# ETAG_v10_3_NOSDTRANS.net
KiCad netlist of a schematic drawn in EAGLE
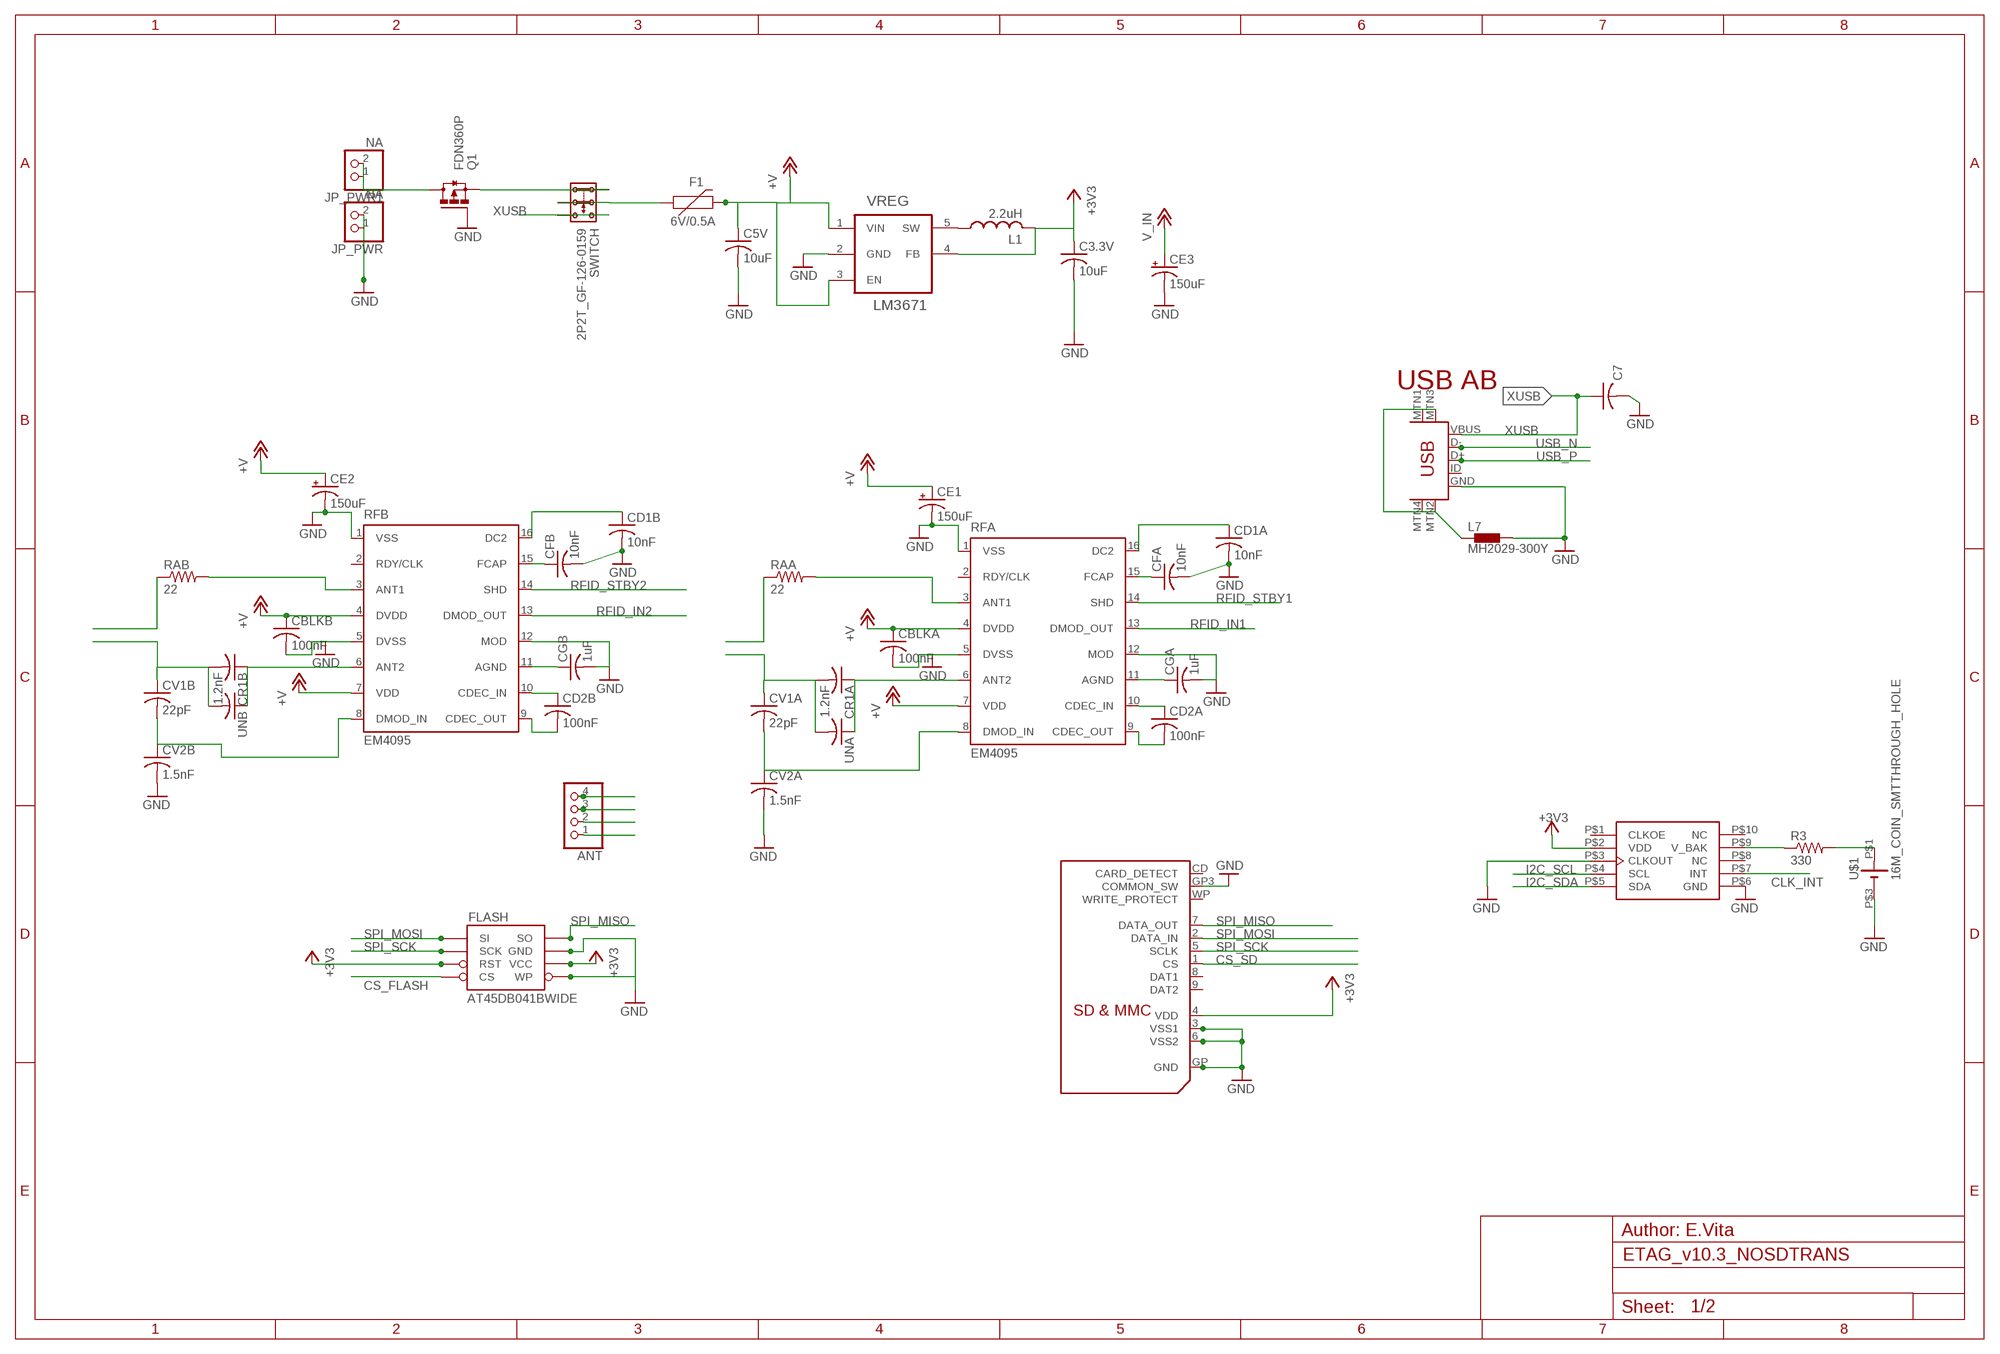
[diagram p0: schematic, sheet 1]
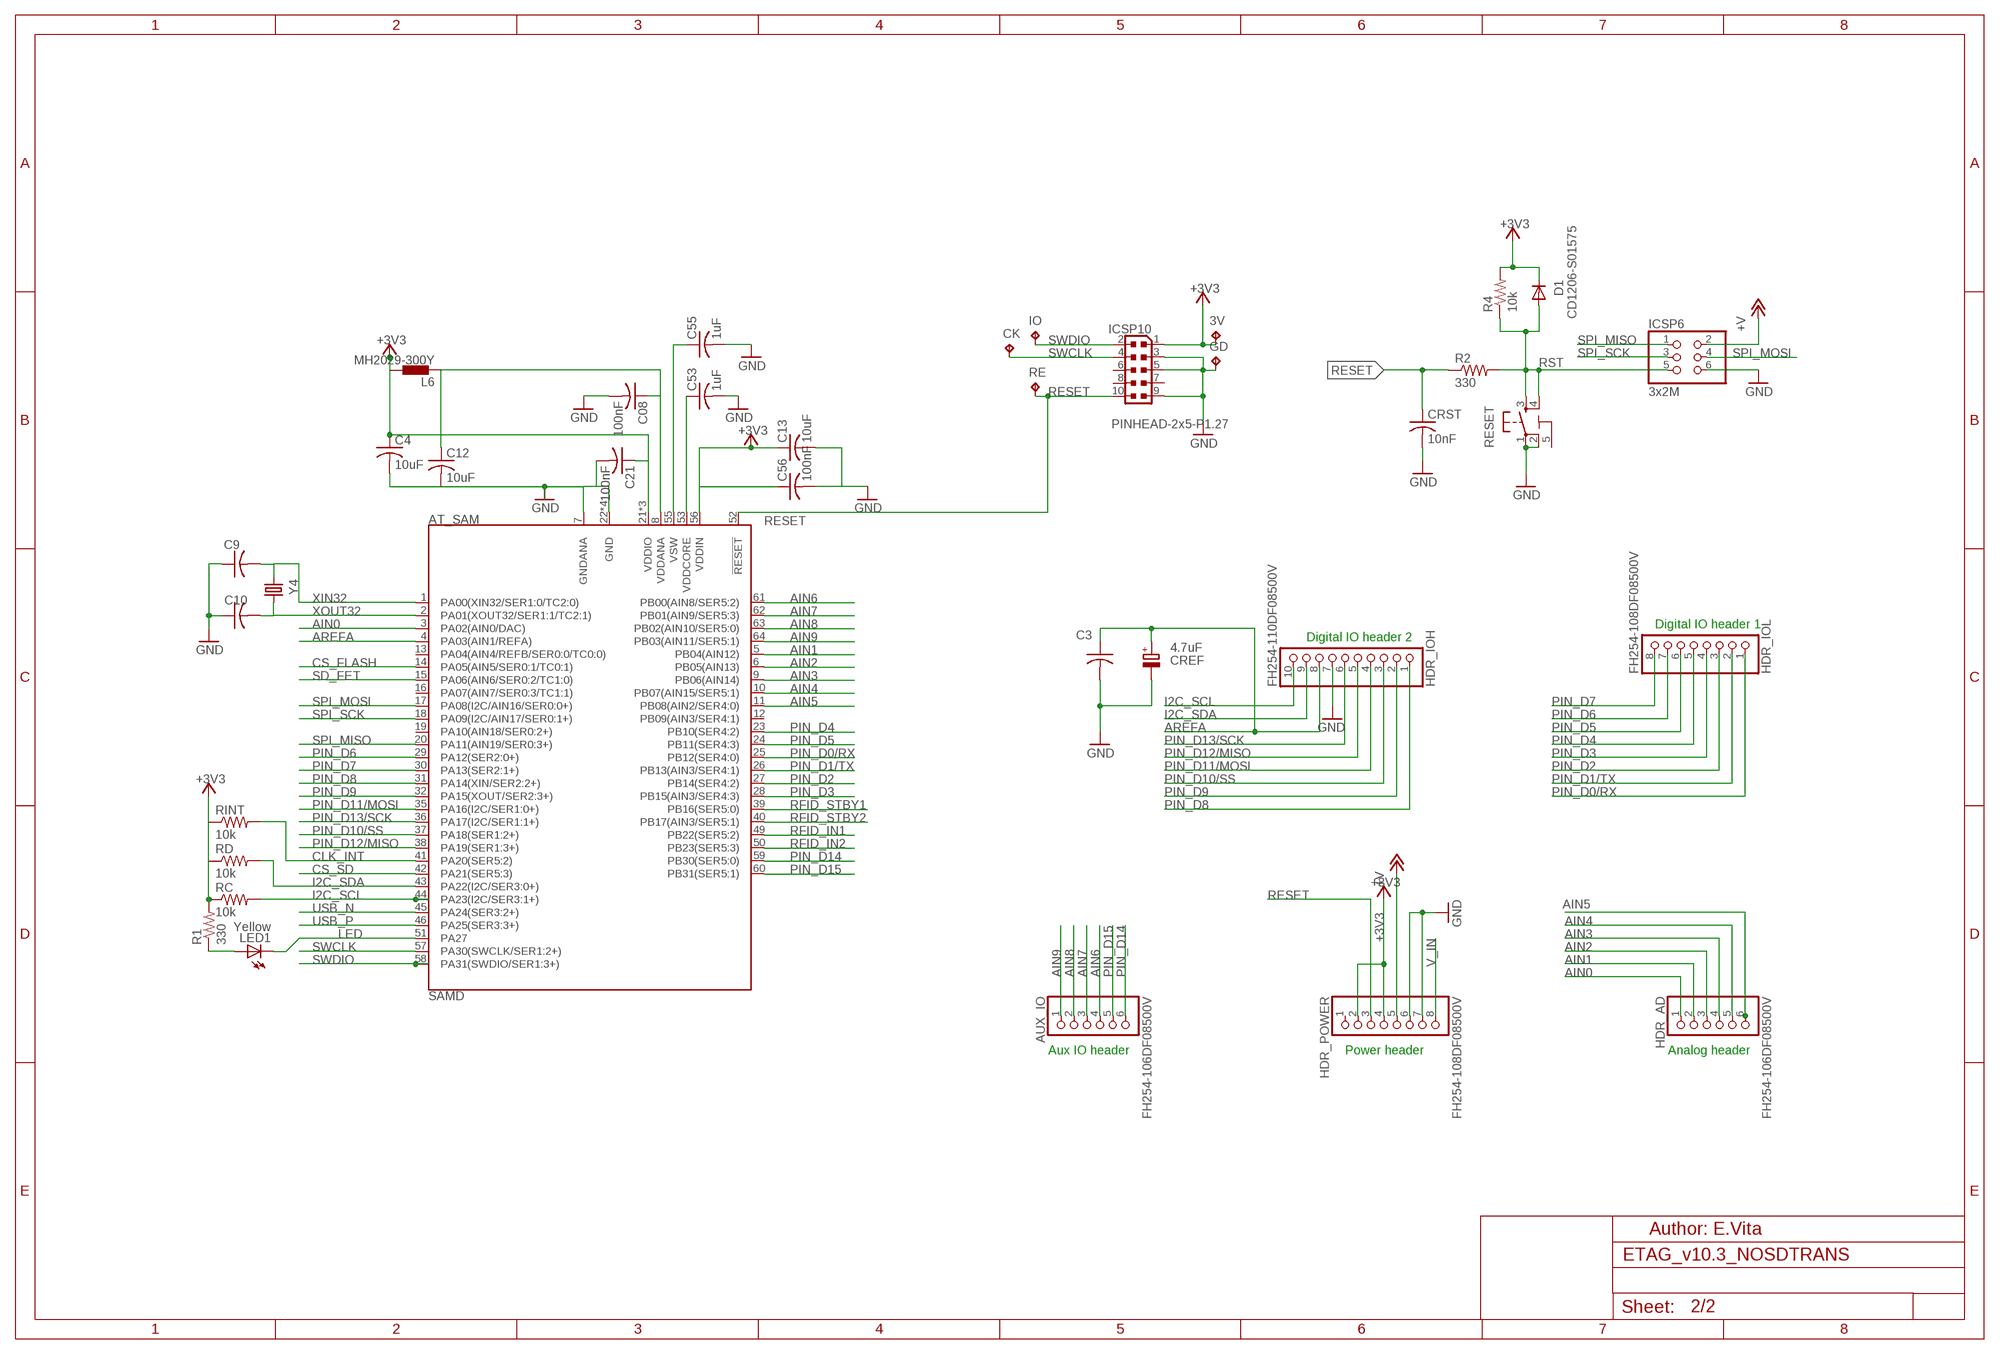
[diagram p1: schematic, sheet 2]

(export (version "E")
  (design (tool "Eeschema 10.0.6"))
  (components
    (comp (ref "ANT")
      (value "PINHD-1X4")
      (footprint "eagle-import:1X04")
      (libsource (lib "eagle-import") (part "PINHD-1X4"))
    )
    (comp (ref "C3.3V")
      (value "10uF")
      (footprint "eagle-import:C0805")
      (libsource (lib "eagle-import") (part "C-USC0805"))
    )
    (comp (ref "C5V")
      (value "10uF")
      (footprint "eagle-import:C0805")
      (libsource (lib "eagle-import") (part "C-USC0805"))
    )
    (comp (ref "C7")
      (value "10nF")
      (footprint "eagle-import:C0603-ROUND")
      (libsource (lib "eagle-import") (part "C-USROUND"))
    )
    (comp (ref "CBLKA")
      (value "100nF")
      (footprint "eagle-import:C0603-ROUND")
      (libsource (lib "eagle-import") (part "C-US"))
    )
    (comp (ref "CBLKB")
      (value "100nF")
      (footprint "eagle-import:C0603-ROUND")
      (libsource (lib "eagle-import") (part "C-US"))
    )
    (comp (ref "CD1A")
      (value "10nF")
      (footprint "eagle-import:C0603-ROUND")
      (libsource (lib "eagle-import") (part "C-US"))
    )
    (comp (ref "CD1B")
      (value "10nF")
      (footprint "eagle-import:C0603-ROUND")
      (libsource (lib "eagle-import") (part "C-USROUND"))
    )
    (comp (ref "CD2A")
      (value "100nF")
      (footprint "eagle-import:C0603-ROUND")
      (libsource (lib "eagle-import") (part "C-US"))
    )
    (comp (ref "CD2B")
      (value "100nF")
      (footprint "eagle-import:C0603-ROUND")
      (libsource (lib "eagle-import") (part "C-US"))
    )
    (comp (ref "CE1")
      (value "150uF")
      (footprint "eagle-import:PANASONIC_C")
      (libsource (lib "eagle-import") (part "CPOL-USC"))
    )
    (comp (ref "CE2")
      (value "150uF")
      (footprint "eagle-import:PANASONIC_C")
      (libsource (lib "eagle-import") (part "CPOL-USC"))
    )
    (comp (ref "CE3")
      (value "150uF")
      (footprint "eagle-import:PANASONIC_C")
      (libsource (lib "eagle-import") (part "CPOL-USC"))
    )
    (comp (ref "CFA")
      (value "10nF")
      (footprint "eagle-import:C0603-ROUND")
      (libsource (lib "eagle-import") (part "C-USROUND"))
    )
    (comp (ref "CFB")
      (value "10nF")
      (footprint "eagle-import:C0603-ROUND")
      (libsource (lib "eagle-import") (part "C-US"))
    )
    (comp (ref "CGA")
      (value "1uF")
      (footprint "eagle-import:C0603-ROUND")
      (libsource (lib "eagle-import") (part "C-US"))
    )
    (comp (ref "CGB")
      (value "1uF")
      (footprint "eagle-import:C0603-ROUND")
      (libsource (lib "eagle-import") (part "C-US"))
    )
    (comp (ref "CR1A")
      (value "1.2nF")
      (footprint "eagle-import:C0603-ROUND")
      (libsource (lib "eagle-import") (part "C-USROUND"))
    )
    (comp (ref "CR1B")
      (value "1.2nF")
      (footprint "eagle-import:C0603-ROUND")
      (libsource (lib "eagle-import") (part "C-US"))
    )
    (comp (ref "CV1A")
      (value "22pF")
      (footprint "eagle-import:C0603-ROUND")
      (libsource (lib "eagle-import") (part "C-US"))
    )
    (comp (ref "CV1B")
      (value "22pF")
      (footprint "eagle-import:C0603-ROUND")
      (libsource (lib "eagle-import") (part "C-US"))
    )
    (comp (ref "CV2A")
      (value "1.5nF")
      (footprint "eagle-import:C0603-ROUND")
      (libsource (lib "eagle-import") (part "C-USROUND"))
    )
    (comp (ref "CV2B")
      (value "1.5nF")
      (footprint "eagle-import:C0603-ROUND")
      (libsource (lib "eagle-import") (part "C-US"))
    )
    (comp (ref "F1")
      (value "6V/0.5A")
      (footprint "eagle-import:1206")
      (libsource (lib "eagle-import") (part "PPTC_6V500MA-2"))
    )
    (comp (ref "FLASH")
      (value "AT45DB041BWIDE")
      (footprint "eagle-import:SO08WIDE")
      (libsource (lib "eagle-import") (part "AT45DB041BWIDE"))
    )
    (comp (ref "JP_PWR")
      (value "NA")
      (footprint "eagle-import:1X02")
      (libsource (lib "eagle-import") (part "PINHD-1X2"))
    )
    (comp (ref "JP_PWR1")
      (value "NA")
      (footprint "eagle-import:1X02")
      (libsource (lib "eagle-import") (part "PINHD-1X2"))
    )
    (comp (ref "L1")
      (value "2.2uH")
      (footprint "eagle-import:SMT_COIL_INDUCTOR_4X4MM")
      (libsource (lib "eagle-import") (part "L-US4X4"))
    )
    (comp (ref "L7")
      (value "MH2029-300Y")
      (footprint "eagle-import:C0805K")
      (libsource (lib "eagle-import") (part "BLM15H0805"))
    )
    (comp (ref "Q1")
      (value "FDN360P")
      (footprint "eagle-import:SUPER-SOT3")
      (libsource (lib "eagle-import") (part "FDN360P"))
    )
    (comp (ref "R3")
      (value "330")
      (footprint "eagle-import:C0603-ROUND")
      (libsource (lib "eagle-import") (part "R-US_ROUND"))
    )
    (comp (ref "RAA")
      (value "22")
      (footprint "eagle-import:R0805")
      (libsource (lib "eagle-import") (part "R-US_R0805"))
    )
    (comp (ref "RAB")
      (value "22")
      (footprint "eagle-import:R0805")
      (libsource (lib "eagle-import") (part "R-US_R0805"))
    )
    (comp (ref "RFA")
      (value "EM4095")
      (footprint "eagle-import:SO16")
      (libsource (lib "eagle-import") (part "EM4095"))
    )
    (comp (ref "RFB")
      (value "EM4095")
      (footprint "eagle-import:SO16")
      (libsource (lib "eagle-import") (part "EM4095"))
    )
    (comp (ref "RTC")
      (value "MC-RTC-RV-3029-C3-I2C")
      (footprint "eagle-import:MC-RTC-C3_SPECIAL")
      (libsource (lib "eagle-import") (part "MC-RTC-RV-3029-C3-I2C"))
    )
    (comp (ref "SD")
      (value "SDMMC06132")
      (footprint "eagle-import:06132")
      (libsource (lib "eagle-import") (part "SDMMC06132"))
    )
    (comp (ref "SWITCH")
      (value "2P2T_GF-126-0159")
      (footprint "eagle-import:2P2T_GF-126-0159")
      (libsource (lib "eagle-import") (part "2P2T_GF-126-0159"))
    )
    (comp (ref "U$1")
      (value "16M_COIN_SMTTHROUGH_HOLE")
      (footprint "eagle-import:16_MM_THROUGH_HOLE")
      (libsource (lib "eagle-import") (part "16M_COIN_SMTTHROUGH_HOLE"))
    )
    (comp (ref "UNA")
      (value "C-US")
      (footprint "eagle-import:C0603-ROUND")
      (libsource (lib "eagle-import") (part "C-US"))
    )
    (comp (ref "UNB")
      (value "C-US")
      (footprint "eagle-import:C0603-ROUND")
      (libsource (lib "eagle-import") (part "C-US"))
    )
    (comp (ref "USB")
      (value "USB-MINIB-5PIN")
      (footprint "eagle-import:USB-MINIB")
      (libsource (lib "eagle-import") (part "USB-MINIB-5PIN"))
    )
    (comp (ref "VREG")
      (value "LM3671")
      (footprint "eagle-import:SOT23-5L")
      (libsource (lib "eagle-import") (part "LM3671_SWITCHING_REGSOT23"))
    )
    (comp (ref "3V")
      (value "TPTP12R")
      (footprint "eagle-import:TP12R")
      (libsource (lib "eagle-import") (part "TPTP12R"))
    )
    (comp (ref "AT_SAM")
      (value "SAMD")
      (footprint "eagle-import:TQFP_10MM_0.5PITCH")
      (libsource (lib "eagle-import") (part "ATSAML21JTQFP_10MM_0.5PITCH"))
    )
    (comp (ref "AUX_IO")
      (value "FH254-106DF08500V")
      (footprint "eagle-import:1X06")
      (fields (field (name "PART_NUMBER") "20TW-535"))
      (libsource (lib "eagle-import") (part "1682_20TW-535_STD"))
    )
    (comp (ref "C3")
      (value "100nF")
      (footprint "eagle-import:C0603-ROUND")
      (libsource (lib "eagle-import") (part "C-USROUND"))
    )
    (comp (ref "C4")
      (value "10uF")
      (footprint "eagle-import:C0805")
      (libsource (lib "eagle-import") (part "C-USC0805"))
    )
    (comp (ref "C08")
      (value "100nF")
      (footprint "eagle-import:C0603-ROUND")
      (libsource (lib "eagle-import") (part "C-USROUND"))
    )
    (comp (ref "C9")
      (value "22pF")
      (footprint "eagle-import:C0603-ROUND")
      (libsource (lib "eagle-import") (part "C-USROUND"))
    )
    (comp (ref "C10")
      (value "22pF")
      (footprint "eagle-import:C0603-ROUND")
      (libsource (lib "eagle-import") (part "C-USROUND"))
    )
    (comp (ref "C12")
      (value "10uF")
      (footprint "eagle-import:C0805")
      (libsource (lib "eagle-import") (part "C-USC0805"))
    )
    (comp (ref "C13")
      (value "10uF")
      (footprint "eagle-import:C0805")
      (libsource (lib "eagle-import") (part "C-USC0805"))
    )
    (comp (ref "C21")
      (value "100nF")
      (footprint "eagle-import:C0603-ROUND")
      (libsource (lib "eagle-import") (part "C-USROUND"))
    )
    (comp (ref "C53")
      (value "1uF")
      (footprint "eagle-import:C0603-ROUND")
      (libsource (lib "eagle-import") (part "C-USROUND"))
    )
    (comp (ref "C55")
      (value "1uF")
      (footprint "eagle-import:C0603-ROUND")
      (libsource (lib "eagle-import") (part "C-USROUND"))
    )
    (comp (ref "C56")
      (value "100nF")
      (footprint "eagle-import:C0603-ROUND")
      (libsource (lib "eagle-import") (part "C-USROUND"))
    )
    (comp (ref "CK")
      (value "TPTP12R")
      (footprint "eagle-import:TP12R")
      (libsource (lib "eagle-import") (part "TPTP12R"))
    )
    (comp (ref "CREF")
      (value "4.7uF")
      (footprint "eagle-import:SMC_A")
      (fields (field (name "PART_NUMBER") "TAJA475M016RNJ"))
      (libsource (lib "eagle-import") (part "0474_TAJA475M016RNJ"))
    )
    (comp (ref "CRST")
      (value "10nF")
      (footprint "eagle-import:C0603-ROUND")
      (libsource (lib "eagle-import") (part "C-USROUND"))
    )
    (comp (ref "D1")
      (value "CD1206-S01575")
      (footprint "eagle-import:MINIMELF")
      (libsource (lib "eagle-import") (part "0012_CD1206-S01575"))
    )
    (comp (ref "GD")
      (value "TPTP12R")
      (footprint "eagle-import:TP12R")
      (libsource (lib "eagle-import") (part "TPTP12R"))
    )
    (comp (ref "HDR_AD")
      (value "FH254-106DF08500V")
      (footprint "eagle-import:1X06")
      (fields (field (name "PART_NUMBER") "20TW-535"))
      (libsource (lib "eagle-import") (part "1682_20TW-535_STD"))
    )
    (comp (ref "HDR_IOH")
      (value "FH254-110DF08500V")
      (footprint "eagle-import:1X10")
      (fields (field (name "PART_NUMBER") "20TW-537"))
      (libsource (lib "eagle-import") (part "1684_20TW-537"))
    )
    (comp (ref "HDR_IOL")
      (value "FH254-108DF08500V")
      (footprint "eagle-import:1X08")
      (fields (field (name "PART_NUMBER") "20TW-536"))
      (libsource (lib "eagle-import") (part "1683_20TW-536"))
    )
    (comp (ref "HDR_POWER")
      (value "FH254-108DF08500V")
      (footprint "eagle-import:1X08")
      (fields (field (name "PART_NUMBER") "20TW-536"))
      (libsource (lib "eagle-import") (part "1683_20TW-536"))
    )
    (comp (ref "ICSP6")
      (value "3x2M")
      (footprint "eagle-import:2X03")
      (fields (field (name "PART_NUMBER") "PH254-203DF118A00V"))
      (libsource (lib "eagle-import") (part "0114_PH254-203DF118A00V"))
    )
    (comp (ref "ICSP10")
      (value "PINHEAD-2x5-P1.27")
      (footprint "eagle-import:PINHEAD_2X05_127")
      (libsource (lib "eagle-import") (part "0171_PH127-205DF055G00AROUND-PADS"))
    )
    (comp (ref "IO")
      (value "TPTP12R")
      (footprint "eagle-import:TP12R")
      (libsource (lib "eagle-import") (part "TPTP12R"))
    )
    (comp (ref "L6")
      (value "MH2029-300Y")
      (footprint "eagle-import:C0805K")
      (libsource (lib "eagle-import") (part "BLM15H0805"))
    )
    (comp (ref "LED1")
      (value "Yellow")
      (footprint "eagle-import:CHIPLED_0805")
      (fields (field (name "PART_NUMBER") "KPT-2012YC"))
      (libsource (lib "eagle-import") (part "0044_KPT-2012YC"))
    )
    (comp (ref "R1")
      (value "330")
      (footprint "eagle-import:C0603-ROUND")
      (libsource (lib "eagle-import") (part "R-US_ROUND"))
    )
    (comp (ref "R2")
      (value "330")
      (footprint "eagle-import:C0603-ROUND")
      (libsource (lib "eagle-import") (part "R-US_ROUND"))
    )
    (comp (ref "R4")
      (value "10k")
      (footprint "eagle-import:C0603-ROUND")
      (libsource (lib "eagle-import") (part "R-US_ROUND"))
    )
    (comp (ref "RC")
      (value "10k")
      (footprint "eagle-import:C0603-ROUND")
      (libsource (lib "eagle-import") (part "R-US_ROUND"))
    )
    (comp (ref "RD")
      (value "10k")
      (footprint "eagle-import:C0603-ROUND")
      (libsource (lib "eagle-import") (part "R-US_ROUND"))
    )
    (comp (ref "RE")
      (value "TPTP12R")
      (footprint "eagle-import:TP12R")
      (libsource (lib "eagle-import") (part "TPTP12R"))
    )
    (comp (ref "RESET")
      (value "TS42031-160R-TR-7260")
      (footprint "eagle-import:TS42")
      (fields (field (name "PART_NUMBER") "IT-1157AHNP-160G-G_GTR"))
      (libsource (lib "eagle-import") (part "0946_TS42031-160W-TR-7260"))
    )
    (comp (ref "RINT")
      (value "10k")
      (footprint "eagle-import:C0603-ROUND")
      (libsource (lib "eagle-import") (part "R-US_ROUND"))
    )
    (comp (ref "Y4")
      (value "32,768Khz")
      (footprint "eagle-import:RESONATOR_EPSON_FC_145")
      (fields (field (name "PART_NUMBER") "ABS07-32.768KHZ-T"))
      (libsource (lib "eagle-import") (part "0213_ABS07-32.768KHZ-T"))
    )
  )
  (nets
    (net (code "1") (name "+3V3") (class "Default")
      (node (ref "3V") (pin "TP") (pinfunction "TP_TP") (pintype "input"))
      (node (ref "AT_SAM") (pin "21") (pinfunction "VDDIO_21") (pintype "bidirectional"))
      (node (ref "AT_SAM") (pin "34") (pinfunction "VDDIO_34") (pintype "bidirectional"))
      (node (ref "AT_SAM") (pin "48") (pinfunction "VDDIO_48") (pintype "bidirectional"))
      (node (ref "AT_SAM") (pin "56") (pinfunction "VDDIN_56") (pintype "bidirectional"))
      (node (ref "C13") (pin "1") (pinfunction "1_1") (pintype "passive"))
      (node (ref "C21") (pin "1") (pinfunction "1_1") (pintype "passive"))
      (node (ref "C3.3V") (pin "1") (pinfunction "1_1") (pintype "passive"))
      (node (ref "C4") (pin "1") (pinfunction "1_1") (pintype "passive"))
      (node (ref "C56") (pin "1") (pinfunction "1_1") (pintype "passive"))
      (node (ref "D1") (pin "C") (pinfunction "C_C") (pintype "passive"))
      (node (ref "FLASH") (pin "3") (pinfunction "RST_3") (pintype "bidirectional"))
      (node (ref "FLASH") (pin "6") (pinfunction "VCC_6") (pintype "bidirectional"))
      (node (ref "HDR_POWER") (pin "2") (pinfunction "2_2") (pintype "passive"))
      (node (ref "HDR_POWER") (pin "4") (pinfunction "4_4") (pintype "passive"))
      (node (ref "ICSP10") (pin "1") (pinfunction "1_1") (pintype "passive"))
      (node (ref "L1") (pin "P$2") (pinfunction "2_P$2") (pintype "passive"))
      (node (ref "L6") (pin "2") (pinfunction "2_2") (pintype "passive"))
      (node (ref "R1") (pin "2") (pinfunction "2_2") (pintype "passive"))
      (node (ref "R4") (pin "2") (pinfunction "2_2") (pintype "passive"))
      (node (ref "RC") (pin "1") (pinfunction "1_1") (pintype "passive"))
      (node (ref "RD") (pin "1") (pinfunction "1_1") (pintype "passive"))
      (node (ref "RINT") (pin "1") (pinfunction "1_1") (pintype "passive"))
      (node (ref "RTC") (pin "P$2") (pinfunction "VDD_P$2") (pintype "power_in"))
      (node (ref "SD") (pin "4") (pinfunction "VDD_4") (pintype "power_in"))
      (node (ref "VREG") (pin "4") (pinfunction "FB_4") (pintype "power_in"))
    )
    (net (code "2") (name "5-GND") (class "Default")
      (node (ref "RESET") (pin "5") (pinfunction "5-GND_5") (pintype "power_in"))
    )
    (net (code "3") (name "AANT") (class "Default")
      (node (ref "ANT") (pin "4") (pinfunction "4_4") (pintype "passive"))
      (node (ref "RAA") (pin "1") (pinfunction "1_1") (pintype "passive"))
    )
    (net (code "4") (name "AIN0") (class "Default")
      (node (ref "AT_SAM") (pin "3") (pinfunction "PA02(AIN0/DAC)_3") (pintype "bidirectional"))
      (node (ref "HDR_AD") (pin "1") (pinfunction "1_1") (pintype "passive"))
    )
    (net (code "5") (name "AIN1") (class "Default")
      (node (ref "AT_SAM") (pin "5") (pinfunction "PB04(AIN12)_5") (pintype "bidirectional"))
      (node (ref "HDR_AD") (pin "2") (pinfunction "2_2") (pintype "passive"))
    )
    (net (code "6") (name "AIN2") (class "Default")
      (node (ref "AT_SAM") (pin "6") (pinfunction "PB05(AIN13)_6") (pintype "bidirectional"))
      (node (ref "HDR_AD") (pin "3") (pinfunction "3_3") (pintype "passive"))
    )
    (net (code "7") (name "AIN3") (class "Default")
      (node (ref "AT_SAM") (pin "9") (pinfunction "PB06(AIN14)_9") (pintype "bidirectional"))
      (node (ref "HDR_AD") (pin "4") (pinfunction "4_4") (pintype "passive"))
    )
    (net (code "8") (name "AIN4") (class "Default")
      (node (ref "AT_SAM") (pin "10") (pinfunction "PB07(AIN15/SER5:1)_10") (pintype "bidirectional"))
      (node (ref "HDR_AD") (pin "5") (pinfunction "5_5") (pintype "passive"))
    )
    (net (code "9") (name "AIN5") (class "Default")
      (node (ref "AT_SAM") (pin "11") (pinfunction "PB08(AIN2/SER4:0)_11") (pintype "bidirectional"))
      (node (ref "HDR_AD") (pin "6") (pinfunction "6_6") (pintype "passive"))
    )
    (net (code "10") (name "AIN6") (class "Default")
      (node (ref "AT_SAM") (pin "61") (pinfunction "PB00(AIN8/SER5:2)_61") (pintype "bidirectional"))
      (node (ref "AUX_IO") (pin "4") (pinfunction "4_4") (pintype "passive"))
    )
    (net (code "11") (name "AIN7") (class "Default")
      (node (ref "AT_SAM") (pin "62") (pinfunction "PB01(AIN9/SER5:3)_62") (pintype "bidirectional"))
      (node (ref "AUX_IO") (pin "3") (pinfunction "3_3") (pintype "passive"))
    )
    (net (code "12") (name "AIN8") (class "Default")
      (node (ref "AT_SAM") (pin "63") (pinfunction "PB02(AIN10/SER5:0)_63") (pintype "bidirectional"))
      (node (ref "AUX_IO") (pin "2") (pinfunction "2_2") (pintype "passive"))
    )
    (net (code "13") (name "AIN9") (class "Default")
      (node (ref "AT_SAM") (pin "64") (pinfunction "PB03(AIN11/SER5:1)_64") (pintype "bidirectional"))
      (node (ref "AUX_IO") (pin "1") (pinfunction "1_1") (pintype "passive"))
    )
    (net (code "14") (name "AREFA") (class "Default")
      (node (ref "AT_SAM") (pin "4") (pinfunction "PA03(AIN1/REFA)_4") (pintype "bidirectional"))
      (node (ref "C3") (pin "1") (pinfunction "1_1") (pintype "passive"))
      (node (ref "CREF") (pin "+") (pinfunction "+_+") (pintype "passive"))
      (node (ref "HDR_IOH") (pin "8") (pinfunction "8_8") (pintype "passive"))
    )
    (net (code "15") (name "BANT") (class "Default")
      (node (ref "ANT") (pin "2") (pinfunction "2_2") (pintype "passive"))
      (node (ref "RAB") (pin "1") (pinfunction "1_1") (pintype "passive"))
    )
    (net (code "16") (name "CLK_INT") (class "Default")
      (node (ref "AT_SAM") (pin "41") (pinfunction "PA20(SER5:2)_41") (pintype "bidirectional"))
      (node (ref "RINT") (pin "2") (pinfunction "2_2") (pintype "passive"))
      (node (ref "RTC") (pin "P$7") (pinfunction "INT_P$7") (pintype "bidirectional"))
    )
    (net (code "17") (name "CS_FLASH") (class "Default")
      (node (ref "AT_SAM") (pin "14") (pinfunction "PA05(AIN5/SER0:1/TC0:1)_14") (pintype "bidirectional"))
      (node (ref "FLASH") (pin "4") (pinfunction "CS_4") (pintype "bidirectional"))
    )
    (net (code "18") (name "CS_SD") (class "Default")
      (node (ref "AT_SAM") (pin "42") (pinfunction "PA21(SER5:3)_42") (pintype "bidirectional"))
      (node (ref "SD") (pin "1") (pinfunction "CS_1") (pintype "input"))
    )
    (net (code "19") (name "CVA") (class "Default")
      (node (ref "ANT") (pin "3") (pinfunction "3_3") (pintype "passive"))
      (node (ref "CR1A") (pin "2") (pinfunction "2_2") (pintype "passive"))
      (node (ref "CV1A") (pin "1") (pinfunction "1_1") (pintype "passive"))
      (node (ref "UNA") (pin "2") (pinfunction "2_2") (pintype "passive"))
    )
    (net (code "20") (name "CVB") (class "Default")
      (node (ref "ANT") (pin "1") (pinfunction "1_1") (pintype "passive"))
      (node (ref "CR1B") (pin "2") (pinfunction "2_2") (pintype "passive"))
      (node (ref "CV1B") (pin "1") (pinfunction "1_1") (pintype "passive"))
      (node (ref "UNB") (pin "2") (pinfunction "2_2") (pintype "passive"))
    )
    (net (code "21") (name "GND") (class "Default")
      (node (ref "AT_SAM") (pin "22") (pinfunction "GND_22") (pintype "bidirectional"))
      (node (ref "AT_SAM") (pin "33") (pinfunction "GND_33") (pintype "bidirectional"))
      (node (ref "AT_SAM") (pin "47") (pinfunction "GND_47") (pintype "bidirectional"))
      (node (ref "AT_SAM") (pin "54") (pinfunction "GND_54") (pintype "bidirectional"))
      (node (ref "AT_SAM") (pin "7") (pinfunction "GNDANA_7") (pintype "bidirectional"))
      (node (ref "C08") (pin "2") (pinfunction "2_2") (pintype "passive"))
      (node (ref "C10") (pin "1") (pinfunction "1_1") (pintype "passive"))
      (node (ref "C12") (pin "2") (pinfunction "2_2") (pintype "passive"))
      (node (ref "C13") (pin "2") (pinfunction "2_2") (pintype "passive"))
      (node (ref "C21") (pin "2") (pinfunction "2_2") (pintype "passive"))
      (node (ref "C3") (pin "2") (pinfunction "2_2") (pintype "passive"))
      (node (ref "C3.3V") (pin "2") (pinfunction "2_2") (pintype "passive"))
      (node (ref "C4") (pin "2") (pinfunction "2_2") (pintype "passive"))
      (node (ref "C53") (pin "2") (pinfunction "2_2") (pintype "passive"))
      (node (ref "C55") (pin "2") (pinfunction "2_2") (pintype "passive"))
      (node (ref "C56") (pin "2") (pinfunction "2_2") (pintype "passive"))
      (node (ref "C5V") (pin "2") (pinfunction "2_2") (pintype "passive"))
      (node (ref "C7") (pin "2") (pinfunction "2_2") (pintype "passive"))
      (node (ref "C9") (pin "1") (pinfunction "1_1") (pintype "passive"))
      (node (ref "CBLKA") (pin "2") (pinfunction "2_2") (pintype "passive"))
      (node (ref "CBLKB") (pin "2") (pinfunction "2_2") (pintype "passive"))
      (node (ref "CD1A") (pin "2") (pinfunction "2_2") (pintype "passive"))
      (node (ref "CD1B") (pin "2") (pinfunction "2_2") (pintype "passive"))
      (node (ref "CE1") (pin "-") (pinfunction "-_-") (pintype "passive"))
      (node (ref "CE2") (pin "-") (pinfunction "-_-") (pintype "passive"))
      (node (ref "CE3") (pin "-") (pinfunction "-_-") (pintype "passive"))
      (node (ref "CFA") (pin "2") (pinfunction "2_2") (pintype "passive"))
      (node (ref "CFB") (pin "2") (pinfunction "2_2") (pintype "passive"))
      (node (ref "CGA") (pin "2") (pinfunction "2_2") (pintype "passive"))
      (node (ref "CGB") (pin "2") (pinfunction "2_2") (pintype "passive"))
      (node (ref "CREF") (pin "-") (pinfunction "-_-") (pintype "passive"))
      (node (ref "CRST") (pin "2") (pinfunction "2_2") (pintype "passive"))
      (node (ref "CV2A") (pin "2") (pinfunction "2_2") (pintype "passive"))
      (node (ref "CV2B") (pin "2") (pinfunction "2_2") (pintype "passive"))
      (node (ref "FLASH") (pin "5") (pinfunction "WP_5") (pintype "bidirectional"))
      (node (ref "FLASH") (pin "7") (pinfunction "GND_7") (pintype "bidirectional"))
      (node (ref "GD") (pin "TP") (pinfunction "TP_TP") (pintype "input"))
      (node (ref "HDR_IOH") (pin "7") (pinfunction "7_7") (pintype "passive"))
      (node (ref "HDR_POWER") (pin "6") (pinfunction "6_6") (pintype "passive"))
      (node (ref "HDR_POWER") (pin "7") (pinfunction "7_7") (pintype "passive"))
      (node (ref "ICSP10") (pin "3") (pinfunction "3_3") (pintype "passive"))
      (node (ref "ICSP10") (pin "5") (pinfunction "5_5") (pintype "passive"))
      (node (ref "ICSP10") (pin "9") (pinfunction "9_9") (pintype "passive"))
      (node (ref "ICSP6") (pin "6") (pinfunction "6_6") (pintype "passive"))
      (node (ref "JP_PWR") (pin "1") (pinfunction "1_1") (pintype "passive"))
      (node (ref "JP_PWR") (pin "2") (pinfunction "2_2") (pintype "passive"))
      (node (ref "L7") (pin "2") (pinfunction "2_2") (pintype "passive"))
      (node (ref "Q1") (pin "1") (pinfunction "G_1") (pintype "passive"))
      (node (ref "RESET") (pin "1") (pinfunction "1_1") (pintype "passive"))
      (node (ref "RESET") (pin "2") (pinfunction "2_2") (pintype "passive"))
      (node (ref "RFA") (pin "1") (pinfunction "VSS_1") (pintype "power_in"))
      (node (ref "RFA") (pin "12") (pinfunction "MOD_12") (pintype "input"))
      (node (ref "RFA") (pin "5") (pinfunction "DVSS_5") (pintype "power_in"))
      (node (ref "RFB") (pin "1") (pinfunction "VSS_1") (pintype "power_in"))
      (node (ref "RFB") (pin "12") (pinfunction "MOD_12") (pintype "input"))
      (node (ref "RFB") (pin "5") (pinfunction "DVSS_5") (pintype "power_in"))
      (node (ref "RTC") (pin "P$3") (pinfunction "CLKOUT_P$3") (pintype "output"))
      (node (ref "RTC") (pin "P$6") (pinfunction "GND_P$6") (pintype "power_in"))
      (node (ref "SD") (pin "3") (pinfunction "VSS1_3") (pintype "power_in"))
      (node (ref "SD") (pin "6") (pinfunction "VSS2_6") (pintype "power_in"))
      (node (ref "SD") (pin "GP") (pinfunction "GND_GP") (pintype "power_in"))
      (node (ref "SD") (pin "GP3") (pinfunction "COMMON_SW_GP3") (pintype "passive"))
      (node (ref "U$1") (pin "P$3") (pinfunction "-_P$3") (pintype "passive"))
      (node (ref "USB") (pin "GND") (pinfunction "GND_GND") (pintype "bidirectional"))
      (node (ref "VREG") (pin "2") (pinfunction "GND_2") (pintype "passive"))
    )
    (net (code "22") (name "I2C_SCL") (class "Default")
      (node (ref "AT_SAM") (pin "44") (pinfunction "PA23(I2C/SER3:1+)_44") (pintype "bidirectional"))
      (node (ref "HDR_IOH") (pin "10") (pinfunction "10_10") (pintype "passive"))
      (node (ref "RC") (pin "2") (pinfunction "2_2") (pintype "passive"))
      (node (ref "RTC") (pin "P$4") (pinfunction "SCL_P$4") (pintype "bidirectional"))
    )
    (net (code "23") (name "I2C_SDA") (class "Default")
      (node (ref "AT_SAM") (pin "43") (pinfunction "PA22(I2C/SER3:0+)_43") (pintype "bidirectional"))
      (node (ref "HDR_IOH") (pin "9") (pinfunction "9_9") (pintype "passive"))
      (node (ref "RD") (pin "2") (pinfunction "2_2") (pintype "passive"))
      (node (ref "RTC") (pin "P$5") (pinfunction "SDA_P$5") (pintype "bidirectional"))
    )
    (net (code "24") (name "LED") (class "Default")
      (node (ref "AT_SAM") (pin "51") (pinfunction "PA27_51") (pintype "bidirectional"))
      (node (ref "LED1") (pin "C") (pinfunction "C_C") (pintype "passive"))
    )
    (net (code "25") (name "Net-(AT_SAM-VDDANA)") (class "Default")
      (node (ref "AT_SAM") (pin "8") (pinfunction "VDDANA_8") (pintype "bidirectional"))
      (node (ref "C08") (pin "1") (pinfunction "1_1") (pintype "passive"))
      (node (ref "C12") (pin "1") (pinfunction "1_1") (pintype "passive"))
      (node (ref "L6") (pin "1") (pinfunction "1_1") (pintype "passive"))
    )
    (net (code "26") (name "Net-(AT_SAM-VDDCORE)") (class "Default")
      (node (ref "AT_SAM") (pin "53") (pinfunction "VDDCORE_53") (pintype "bidirectional"))
      (node (ref "C53") (pin "1") (pinfunction "1_1") (pintype "passive"))
    )
    (net (code "27") (name "Net-(AT_SAM-VSW)") (class "Default")
      (node (ref "AT_SAM") (pin "55") (pinfunction "VSW_55") (pintype "bidirectional"))
      (node (ref "C55") (pin "1") (pinfunction "1_1") (pintype "passive"))
    )
    (net (code "28") (name "Net-(L1-1)") (class "Default")
      (node (ref "L1") (pin "P$1") (pinfunction "1_P$1") (pintype "passive"))
      (node (ref "VREG") (pin "5") (pinfunction "SW_5") (pintype "power_in"))
    )
    (net (code "29") (name "Net-(LED1-PadA)") (class "Default")
      (node (ref "LED1") (pin "A") (pinfunction "A_A") (pintype "passive"))
      (node (ref "R1") (pin "1") (pinfunction "1_1") (pintype "passive"))
    )
    (net (code "30") (name "Net-(Q1-D)") (class "Default")
      (node (ref "JP_PWR1") (pin "1") (pinfunction "1_1") (pintype "passive"))
      (node (ref "JP_PWR1") (pin "2") (pinfunction "2_2") (pintype "passive"))
      (node (ref "Q1") (pin "3") (pinfunction "D_3") (pintype "passive"))
    )
    (net (code "31") (name "Net-(Q1-S)") (class "Default")
      (node (ref "Q1") (pin "2") (pinfunction "S_2") (pintype "passive"))
      (node (ref "SWITCH") (pin "P1A") (pinfunction "1.1_P1A") (pintype "passive"))
      (node (ref "SWITCH") (pin "P1B") (pinfunction "1.2_P1B") (pintype "passive"))
    )
    (net (code "32") (name "Net-(RFA-AGND)") (class "Default")
      (node (ref "CGA") (pin "1") (pinfunction "1_1") (pintype "passive"))
      (node (ref "RFA") (pin "11") (pinfunction "AGND_11") (pintype "power_in"))
    )
    (net (code "33") (name "Net-(RFA-ANT1)") (class "Default")
      (node (ref "RAA") (pin "2") (pinfunction "2_2") (pintype "passive"))
      (node (ref "RFA") (pin "3") (pinfunction "ANT1_3") (pintype "passive"))
    )
    (net (code "34") (name "Net-(RFA-ANT2)") (class "Default")
      (node (ref "CR1A") (pin "1") (pinfunction "1_1") (pintype "passive"))
      (node (ref "RFA") (pin "6") (pinfunction "ANT2_6") (pintype "passive"))
      (node (ref "UNA") (pin "1") (pinfunction "1_1") (pintype "passive"))
    )
    (net (code "35") (name "Net-(RFA-CDEC_IN)") (class "Default")
      (node (ref "CD2A") (pin "1") (pinfunction "1_1") (pintype "passive"))
      (node (ref "RFA") (pin "10") (pinfunction "CDEC_IN_10") (pintype "input"))
    )
    (net (code "36") (name "Net-(RFA-CDEC_OUT)") (class "Default")
      (node (ref "CD2A") (pin "2") (pinfunction "2_2") (pintype "passive"))
      (node (ref "RFA") (pin "9") (pinfunction "CDEC_OUT_9") (pintype "output"))
    )
    (net (code "37") (name "Net-(RFA-DC2)") (class "Default")
      (node (ref "CD1A") (pin "1") (pinfunction "1_1") (pintype "passive"))
      (node (ref "RFA") (pin "16") (pinfunction "DC2_16") (pintype "passive"))
    )
    (net (code "38") (name "Net-(RFA-DMOD_IN)") (class "Default")
      (node (ref "CV1A") (pin "2") (pinfunction "2_2") (pintype "passive"))
      (node (ref "CV2A") (pin "1") (pinfunction "1_1") (pintype "passive"))
      (node (ref "RFA") (pin "8") (pinfunction "DMOD_IN_8") (pintype "input"))
    )
    (net (code "39") (name "Net-(RFA-FCAP)") (class "Default")
      (node (ref "CFA") (pin "1") (pinfunction "1_1") (pintype "passive"))
      (node (ref "RFA") (pin "15") (pinfunction "FCAP_15") (pintype "passive"))
    )
    (net (code "40") (name "Net-(RFB-AGND)") (class "Default")
      (node (ref "CGB") (pin "1") (pinfunction "1_1") (pintype "passive"))
      (node (ref "RFB") (pin "11") (pinfunction "AGND_11") (pintype "power_in"))
    )
    (net (code "41") (name "Net-(RFB-ANT1)") (class "Default")
      (node (ref "RAB") (pin "2") (pinfunction "2_2") (pintype "passive"))
      (node (ref "RFB") (pin "3") (pinfunction "ANT1_3") (pintype "passive"))
    )
    (net (code "42") (name "Net-(RFB-ANT2)") (class "Default")
      (node (ref "CR1B") (pin "1") (pinfunction "1_1") (pintype "passive"))
      (node (ref "RFB") (pin "6") (pinfunction "ANT2_6") (pintype "passive"))
      (node (ref "UNB") (pin "1") (pinfunction "1_1") (pintype "passive"))
    )
    (net (code "43") (name "Net-(RFB-CDEC_IN)") (class "Default")
      (node (ref "CD2B") (pin "1") (pinfunction "1_1") (pintype "passive"))
      (node (ref "RFB") (pin "10") (pinfunction "CDEC_IN_10") (pintype "input"))
    )
    (net (code "44") (name "Net-(RFB-CDEC_OUT)") (class "Default")
      (node (ref "CD2B") (pin "2") (pinfunction "2_2") (pintype "passive"))
      (node (ref "RFB") (pin "9") (pinfunction "CDEC_OUT_9") (pintype "output"))
    )
    (net (code "45") (name "Net-(RFB-DC2)") (class "Default")
      (node (ref "CD1B") (pin "1") (pinfunction "1_1") (pintype "passive"))
      (node (ref "RFB") (pin "16") (pinfunction "DC2_16") (pintype "passive"))
    )
    (net (code "46") (name "Net-(RFB-DMOD_IN)") (class "Default")
      (node (ref "CV1B") (pin "2") (pinfunction "2_2") (pintype "passive"))
      (node (ref "CV2B") (pin "1") (pinfunction "1_1") (pintype "passive"))
      (node (ref "RFB") (pin "8") (pinfunction "DMOD_IN_8") (pintype "input"))
    )
    (net (code "47") (name "Net-(RFB-FCAP)") (class "Default")
      (node (ref "CFB") (pin "1") (pinfunction "1_1") (pintype "passive"))
      (node (ref "RFB") (pin "15") (pinfunction "FCAP_15") (pintype "passive"))
    )
    (net (code "48") (name "Net-(RTC-V_BAK)") (class "Default")
      (node (ref "R3") (pin "1") (pinfunction "1_1") (pintype "passive"))
      (node (ref "RTC") (pin "P$9") (pinfunction "V_BAK_P$9") (pintype "power_in"))
    )
    (net (code "49") (name "Net-(SWITCH-2.1)") (class "Default")
      (node (ref "F1") (pin "1") (pinfunction "1_1") (pintype "bidirectional"))
      (node (ref "SWITCH") (pin "P2A") (pinfunction "2.1_P2A") (pintype "passive"))
      (node (ref "SWITCH") (pin "P2B") (pinfunction "2.2_P2B") (pintype "passive"))
    )
    (net (code "50") (name "Net-(U$1-+)") (class "Default")
      (node (ref "R3") (pin "2") (pinfunction "2_2") (pintype "passive"))
      (node (ref "U$1") (pin "P$1") (pinfunction "+_P$1") (pintype "passive"))
    )
    (net (code "51") (name "Net-(USB-MTN1)") (class "Default")
      (node (ref "L7") (pin "1") (pinfunction "1_1") (pintype "passive"))
      (node (ref "USB") (pin "MTN1") (pinfunction "MTN2_MTN1") (pintype "bidirectional"))
      (node (ref "USB") (pin "MTN2") (pinfunction "MTN3_MTN2") (pintype "bidirectional"))
      (node (ref "USB") (pin "MTN3") (pinfunction "MTN1_MTN3") (pintype "bidirectional"))
      (node (ref "USB") (pin "MTN4") (pinfunction "MTN4_MTN4") (pintype "bidirectional"))
    )
    (net (code "52") (name "PIN_D0{slash}RX") (class "Default")
      (node (ref "AT_SAM") (pin "25") (pinfunction "PB12(SER4:0)_25") (pintype "bidirectional"))
      (node (ref "HDR_IOL") (pin "1") (pinfunction "1_1") (pintype "passive"))
    )
    (net (code "53") (name "PIN_D1{slash}TX") (class "Default")
      (node (ref "AT_SAM") (pin "26") (pinfunction "PB13(AIN3/SER4:1)_26") (pintype "bidirectional"))
      (node (ref "HDR_IOL") (pin "2") (pinfunction "2_2") (pintype "passive"))
    )
    (net (code "54") (name "PIN_D2") (class "Default")
      (node (ref "AT_SAM") (pin "27") (pinfunction "PB14(SER4:2)_27") (pintype "bidirectional"))
      (node (ref "HDR_IOL") (pin "3") (pinfunction "3_3") (pintype "passive"))
    )
    (net (code "55") (name "PIN_D3") (class "Default")
      (node (ref "AT_SAM") (pin "28") (pinfunction "PB15(AIN3/SER4:3)_28") (pintype "bidirectional"))
      (node (ref "HDR_IOL") (pin "4") (pinfunction "4_4") (pintype "passive"))
    )
    (net (code "56") (name "PIN_D4") (class "Default")
      (node (ref "AT_SAM") (pin "23") (pinfunction "PB10(SER4:2)_23") (pintype "bidirectional"))
      (node (ref "HDR_IOL") (pin "5") (pinfunction "5_5") (pintype "passive"))
    )
    (net (code "57") (name "PIN_D5") (class "Default")
      (node (ref "AT_SAM") (pin "24") (pinfunction "PB11(SER4:3)_24") (pintype "bidirectional"))
      (node (ref "HDR_IOL") (pin "6") (pinfunction "6_6") (pintype "passive"))
    )
    (net (code "58") (name "PIN_D6") (class "Default")
      (node (ref "AT_SAM") (pin "29") (pinfunction "PA12(SER2:0+)_29") (pintype "bidirectional"))
      (node (ref "HDR_IOL") (pin "7") (pinfunction "7_7") (pintype "passive"))
    )
    (net (code "59") (name "PIN_D7") (class "Default")
      (node (ref "AT_SAM") (pin "30") (pinfunction "PA13(SER2:1+)_30") (pintype "bidirectional"))
      (node (ref "HDR_IOL") (pin "8") (pinfunction "8_8") (pintype "passive"))
    )
    (net (code "60") (name "PIN_D8") (class "Default")
      (node (ref "AT_SAM") (pin "31") (pinfunction "PA14(XIN/SER2:2+)_31") (pintype "bidirectional"))
      (node (ref "HDR_IOH") (pin "1") (pinfunction "1_1") (pintype "passive"))
    )
    (net (code "61") (name "PIN_D9") (class "Default")
      (node (ref "AT_SAM") (pin "32") (pinfunction "PA15(XOUT/SER2:3+)_32") (pintype "bidirectional"))
      (node (ref "HDR_IOH") (pin "2") (pinfunction "2_2") (pintype "passive"))
    )
    (net (code "62") (name "PIN_D10{slash}SS") (class "Default")
      (node (ref "AT_SAM") (pin "37") (pinfunction "PA18(SER1:2+)_37") (pintype "bidirectional"))
      (node (ref "HDR_IOH") (pin "3") (pinfunction "3_3") (pintype "passive"))
    )
    (net (code "63") (name "PIN_D11{slash}MOSI") (class "Default")
      (node (ref "AT_SAM") (pin "35") (pinfunction "PA16(I2C/SER1:0+)_35") (pintype "bidirectional"))
      (node (ref "HDR_IOH") (pin "4") (pinfunction "4_4") (pintype "passive"))
    )
    (net (code "64") (name "PIN_D12{slash}MISO") (class "Default")
      (node (ref "AT_SAM") (pin "38") (pinfunction "PA19(SER1:3+)_38") (pintype "bidirectional"))
      (node (ref "HDR_IOH") (pin "5") (pinfunction "5_5") (pintype "passive"))
    )
    (net (code "65") (name "PIN_D13{slash}SCK") (class "Default")
      (node (ref "AT_SAM") (pin "36") (pinfunction "PA17(I2C/SER1:1+)_36") (pintype "bidirectional"))
      (node (ref "HDR_IOH") (pin "6") (pinfunction "6_6") (pintype "passive"))
    )
    (net (code "66") (name "PIN_D14") (class "Default")
      (node (ref "AT_SAM") (pin "59") (pinfunction "PB30(SER5:0)_59") (pintype "bidirectional"))
      (node (ref "AUX_IO") (pin "6") (pinfunction "6_6") (pintype "passive"))
    )
    (net (code "67") (name "PIN_D15") (class "Default")
      (node (ref "AT_SAM") (pin "60") (pinfunction "PB31(SER5:1)_60") (pintype "bidirectional"))
      (node (ref "AUX_IO") (pin "5") (pinfunction "5_5") (pintype "passive"))
    )
    (net (code "68") (name "RESET") (class "Default")
      (node (ref "AT_SAM") (pin "52") (pinfunction "~{RESET}_52") (pintype "bidirectional"))
      (node (ref "CRST") (pin "1") (pinfunction "1_1") (pintype "passive"))
      (node (ref "HDR_POWER") (pin "3") (pinfunction "3_3") (pintype "passive"))
      (node (ref "ICSP10") (pin "10") (pinfunction "10_10") (pintype "passive"))
      (node (ref "R2") (pin "1") (pinfunction "1_1") (pintype "passive"))
      (node (ref "RE") (pin "TP") (pinfunction "TP_TP") (pintype "input"))
    )
    (net (code "69") (name "RFID_IN1") (class "Default")
      (node (ref "AT_SAM") (pin "49") (pinfunction "PB22(SER5:2)_49") (pintype "bidirectional"))
      (node (ref "RFA") (pin "13") (pinfunction "DMOD_OUT_13") (pintype "output"))
    )
    (net (code "70") (name "RFID_IN2") (class "Default")
      (node (ref "AT_SAM") (pin "50") (pinfunction "PB23(SER5:3)_50") (pintype "bidirectional"))
      (node (ref "RFB") (pin "13") (pinfunction "DMOD_OUT_13") (pintype "output"))
    )
    (net (code "71") (name "RFID_STBY1") (class "Default")
      (node (ref "AT_SAM") (pin "39") (pinfunction "PB16(SER5:0)_39") (pintype "bidirectional"))
      (node (ref "RFA") (pin "14") (pinfunction "SHD_14") (pintype "input"))
    )
    (net (code "72") (name "RFID_STBY2") (class "Default")
      (node (ref "AT_SAM") (pin "40") (pinfunction "PB17(AIN3/SER5:1)_40") (pintype "bidirectional"))
      (node (ref "RFB") (pin "14") (pinfunction "SHD_14") (pintype "input"))
    )
    (net (code "73") (name "RST") (class "Default")
      (node (ref "D1") (pin "A") (pinfunction "A_A") (pintype "passive"))
      (node (ref "ICSP6") (pin "5") (pinfunction "5_5") (pintype "passive"))
      (node (ref "R2") (pin "2") (pinfunction "2_2") (pintype "passive"))
      (node (ref "R4") (pin "1") (pinfunction "1_1") (pintype "passive"))
      (node (ref "RESET") (pin "3") (pinfunction "3_3") (pintype "passive"))
      (node (ref "RESET") (pin "4") (pinfunction "4_4") (pintype "passive"))
    )
    (net (code "74") (name "SD_FET") (class "Default")
      (node (ref "AT_SAM") (pin "15") (pinfunction "PA06(AIN6/SER0:2/TC1:0)_15") (pintype "bidirectional"))
    )
    (net (code "75") (name "SPI_MISO") (class "Default")
      (node (ref "AT_SAM") (pin "20") (pinfunction "PA11(AIN19/SER0:3+)_20") (pintype "bidirectional"))
      (node (ref "FLASH") (pin "8") (pinfunction "SO_8") (pintype "bidirectional"))
      (node (ref "ICSP6") (pin "1") (pinfunction "1_1") (pintype "passive"))
      (node (ref "SD") (pin "7") (pinfunction "DATA_OUT_7") (pintype "output"))
    )
    (net (code "76") (name "SPI_MOSI") (class "Default")
      (node (ref "AT_SAM") (pin "17") (pinfunction "PA08(I2C/AIN16/SER0:0+)_17") (pintype "bidirectional"))
      (node (ref "FLASH") (pin "1") (pinfunction "SI_1") (pintype "bidirectional"))
      (node (ref "ICSP6") (pin "4") (pinfunction "4_4") (pintype "passive"))
      (node (ref "SD") (pin "2") (pinfunction "DATA_IN_2") (pintype "input"))
    )
    (net (code "77") (name "SPI_SCK") (class "Default")
      (node (ref "AT_SAM") (pin "18") (pinfunction "PA09(I2C/AIN17/SER0:1+)_18") (pintype "bidirectional"))
      (node (ref "FLASH") (pin "2") (pinfunction "SCK_2") (pintype "bidirectional"))
      (node (ref "ICSP6") (pin "3") (pinfunction "3_3") (pintype "passive"))
      (node (ref "SD") (pin "5") (pinfunction "SCLK_5") (pintype "input"))
    )
    (net (code "78") (name "SWCLK") (class "Default")
      (node (ref "AT_SAM") (pin "57") (pinfunction "PA30(SWCLK/SER1:2+)_57") (pintype "bidirectional"))
      (node (ref "CK") (pin "TP") (pinfunction "TP_TP") (pintype "input"))
      (node (ref "ICSP10") (pin "4") (pinfunction "4_4") (pintype "passive"))
    )
    (net (code "79") (name "SWDIO") (class "Default")
      (node (ref "AT_SAM") (pin "58") (pinfunction "PA31(SWDIO/SER1:3+)_58") (pintype "bidirectional"))
      (node (ref "ICSP10") (pin "2") (pinfunction "2_2") (pintype "passive"))
      (node (ref "IO") (pin "TP") (pinfunction "TP_TP") (pintype "input"))
    )
    (net (code "80") (name "USB_N") (class "Default")
      (node (ref "AT_SAM") (pin "45") (pinfunction "PA24(SER3:2+)_45") (pintype "bidirectional"))
      (node (ref "USB") (pin "D-") (pinfunction "D-_D-") (pintype "bidirectional"))
    )
    (net (code "81") (name "USB_P") (class "Default")
      (node (ref "AT_SAM") (pin "46") (pinfunction "PA25(SER3:3+)_46") (pintype "bidirectional"))
      (node (ref "USB") (pin "D+") (pinfunction "D+_D+") (pintype "bidirectional"))
    )
    (net (code "82") (name "V_IN") (class "Default")
      (node (ref "C5V") (pin "1") (pinfunction "1_1") (pintype "passive"))
      (node (ref "CBLKA") (pin "1") (pinfunction "1_1") (pintype "passive"))
      (node (ref "CBLKB") (pin "1") (pinfunction "1_1") (pintype "passive"))
      (node (ref "CE1") (pin "+") (pinfunction "+_+") (pintype "passive"))
      (node (ref "CE2") (pin "+") (pinfunction "+_+") (pintype "passive"))
      (node (ref "CE3") (pin "+") (pinfunction "+_+") (pintype "passive"))
      (node (ref "F1") (pin "2") (pinfunction "2_2") (pintype "bidirectional"))
      (node (ref "HDR_POWER") (pin "5") (pinfunction "5_5") (pintype "passive"))
      (node (ref "HDR_POWER") (pin "8") (pinfunction "8_8") (pintype "passive"))
      (node (ref "ICSP6") (pin "2") (pinfunction "2_2") (pintype "passive"))
      (node (ref "RFA") (pin "4") (pinfunction "DVDD_4") (pintype "power_in"))
      (node (ref "RFA") (pin "7") (pinfunction "VDD_7") (pintype "power_in"))
      (node (ref "RFB") (pin "4") (pinfunction "DVDD_4") (pintype "power_in"))
      (node (ref "RFB") (pin "7") (pinfunction "VDD_7") (pintype "power_in"))
      (node (ref "VREG") (pin "1") (pinfunction "VIN_1") (pintype "power_in"))
      (node (ref "VREG") (pin "3") (pinfunction "EN_3") (pintype "input"))
    )
    (net (code "83") (name "XIN32") (class "Default")
      (node (ref "AT_SAM") (pin "1") (pinfunction "PA00(XIN32/SER1:0/TC2:0)_1") (pintype "bidirectional"))
      (node (ref "C9") (pin "2") (pinfunction "2_2") (pintype "passive"))
      (node (ref "Y4") (pin "P$1") (pinfunction "1_P$1") (pintype "bidirectional"))
    )
    (net (code "84") (name "XOUT32") (class "Default")
      (node (ref "AT_SAM") (pin "2") (pinfunction "PA01(XOUT32/SER1:1/TC2:1)_2") (pintype "bidirectional"))
      (node (ref "C10") (pin "2") (pinfunction "2_2") (pintype "passive"))
      (node (ref "Y4") (pin "P$2") (pinfunction "2_P$2") (pintype "bidirectional"))
    )
    (net (code "85") (name "XUSB") (class "Default")
      (node (ref "C7") (pin "1") (pinfunction "1_1") (pintype "passive"))
      (node (ref "SWITCH") (pin "P3A") (pinfunction "3.1_P3A") (pintype "passive"))
      (node (ref "SWITCH") (pin "P3B") (pinfunction "3.2_P3B") (pintype "passive"))
      (node (ref "USB") (pin "VBUS") (pinfunction "VBUS_VBUS") (pintype "bidirectional"))
    )
    (net (code "86") (name "unconnected-(AT_SAM-PA04(AIN4{slash}REFB{slash}SER0:0{slash}TC0:0)-Pad13)") (class "Default")
      (node (ref "AT_SAM") (pin "13") (pinfunction "PA04(AIN4/REFB/SER0:0/TC0:0)_13") (pintype "bidirectional"))
    )
    (net (code "87") (name "unconnected-(AT_SAM-PA07(AIN7{slash}SER0:3{slash}TC1:1)-Pad16)") (class "Default")
      (node (ref "AT_SAM") (pin "16") (pinfunction "PA07(AIN7/SER0:3/TC1:1)_16") (pintype "bidirectional"))
    )
    (net (code "88") (name "unconnected-(AT_SAM-PA10(AIN18{slash}SER0:2+)-Pad19)") (class "Default")
      (node (ref "AT_SAM") (pin "19") (pinfunction "PA10(AIN18/SER0:2+)_19") (pintype "bidirectional"))
    )
    (net (code "89") (name "unconnected-(AT_SAM-PB09(AIN3{slash}SER4:1)-Pad12)") (class "Default")
      (node (ref "AT_SAM") (pin "12") (pinfunction "PB09(AIN3/SER4:1)_12") (pintype "bidirectional"))
    )
    (net (code "90") (name "unconnected-(HDR_POWER-Pad1)") (class "Default")
      (node (ref "HDR_POWER") (pin "1") (pinfunction "1_1") (pintype "passive"))
    )
    (net (code "91") (name "unconnected-(ICSP10-Pad6)") (class "Default")
      (node (ref "ICSP10") (pin "6") (pinfunction "6_6") (pintype "passive"))
    )
    (net (code "92") (name "unconnected-(ICSP10-Pad7)") (class "Default")
      (node (ref "ICSP10") (pin "7") (pinfunction "7_7") (pintype "passive"))
    )
    (net (code "93") (name "unconnected-(ICSP10-Pad8)") (class "Default")
      (node (ref "ICSP10") (pin "8") (pinfunction "8_8") (pintype "passive"))
    )
    (net (code "94") (name "unconnected-(RFA-RDY{slash}CLK-Pad2)") (class "Default")
      (node (ref "RFA") (pin "2") (pinfunction "RDY/CLK_2") (pintype "output"))
    )
    (net (code "95") (name "unconnected-(RFB-RDY{slash}CLK-Pad2)") (class "Default")
      (node (ref "RFB") (pin "2") (pinfunction "RDY/CLK_2") (pintype "output"))
    )
    (net (code "96") (name "unconnected-(RTC-CLKOE-PadP$1)") (class "Default")
      (node (ref "RTC") (pin "P$1") (pinfunction "CLKOE_P$1") (pintype "bidirectional"))
    )
    (net (code "97") (name "unconnected-(RTC-NC-PadP$8)") (class "Default")
      (node (ref "RTC") (pin "P$8") (pinfunction "NC_P$8") (pintype "no_connect"))
    )
    (net (code "98") (name "unconnected-(RTC-NC-PadP$10)") (class "Default")
      (node (ref "RTC") (pin "P$10") (pinfunction "NC_P$10") (pintype "no_connect"))
    )
    (net (code "99") (name "unconnected-(SD-CARD_DETECT-PadCD)") (class "Default")
      (node (ref "SD") (pin "CD") (pinfunction "CARD_DETECT_CD") (pintype "passive"))
    )
    (net (code "100") (name "unconnected-(SD-DAT1-Pad8)") (class "Default")
      (node (ref "SD") (pin "8") (pinfunction "DAT1_8") (pintype "bidirectional"))
    )
    (net (code "101") (name "unconnected-(SD-DAT2-Pad9)") (class "Default")
      (node (ref "SD") (pin "9") (pinfunction "DAT2_9") (pintype "bidirectional"))
    )
    (net (code "102") (name "unconnected-(SD-WRITE_PROTECT-PadWP)") (class "Default")
      (node (ref "SD") (pin "WP") (pinfunction "WRITE_PROTECT_WP") (pintype "passive"))
    )
    (net (code "103") (name "unconnected-(USB-PadID)") (class "Default")
      (node (ref "USB") (pin "ID") (pinfunction "ID_ID") (pintype "bidirectional"))
    )
  )
)
